# cc2650_rev1-1.net
KiCad netlist of a schematic drawn in EAGLE
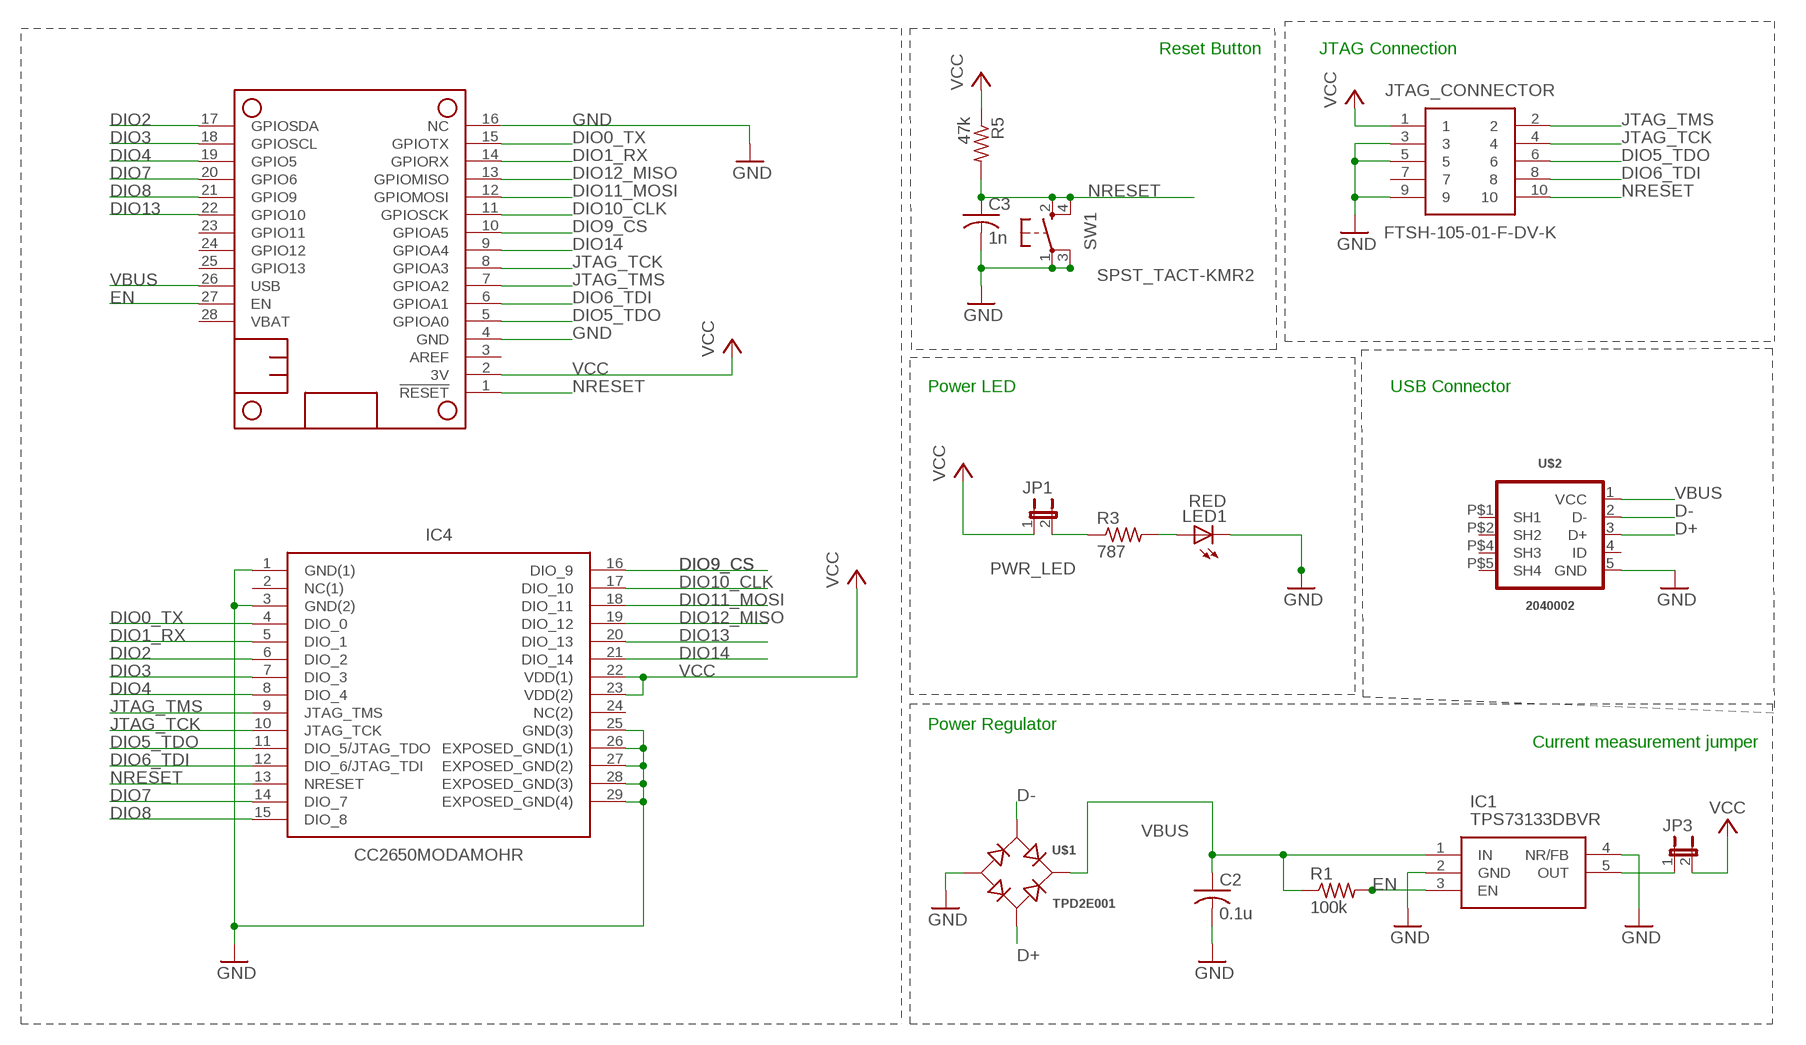
[diagram p0: schematic, sheet 1]
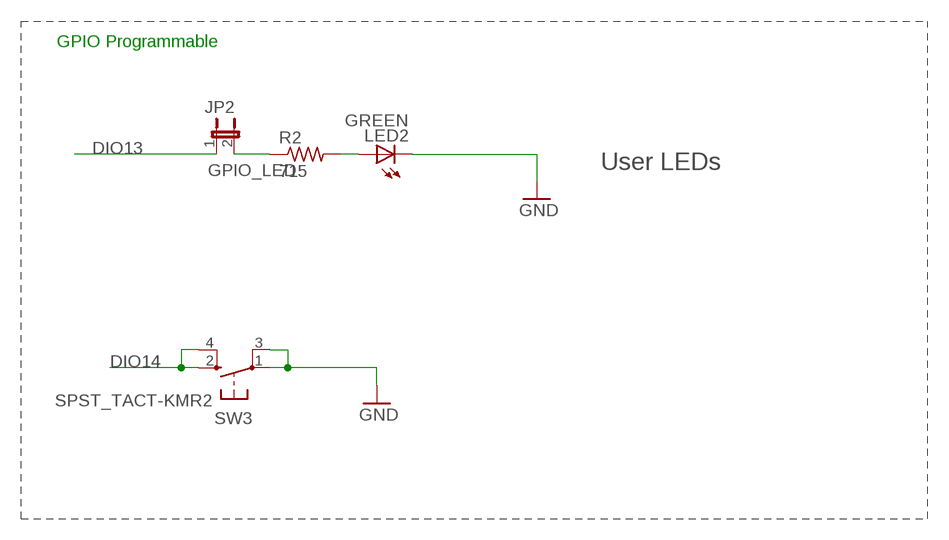
[diagram p1: schematic, sheet 2]

(export (version "E")
  (design (tool "Eeschema 10.0.6"))
  (components
    (comp (ref "C2")
      (value "0.1u")
      (footprint "eagle-import:C1206")
      (fields (field (name "MF") "VISHAY/VITRAMON") (field (name "MPN") "VJ1206Y102KXBAC"))
      (libsource (lib "eagle-import") (part "C-USC1206"))
    )
    (comp (ref "C3")
      (value "1n")
      (footprint "eagle-import:C1206")
      (fields (field (name "MF") "VISHAY/VITRAMON") (field (name "MPN") "VJ1206Y102KXBAC"))
      (libsource (lib "eagle-import") (part "C-USC1206"))
    )
    (comp (ref "IC1")
      (value "TPS73133DBVR")
      (footprint "eagle-import:SOT95P280X145-5N")
      (fields (field (name "RS_PART_NUMBER") "6613970"))
      (libsource (lib "eagle-import") (part "TPS73133DBVR"))
    )
    (comp (ref "IC4")
      (value "CC2650MODAMOHR")
      (footprint "eagle-import:MOH0029A")
      (libsource (lib "eagle-import") (part "CC2650MODAMOHR"))
    )
    (comp (ref "JP1")
      (value "PWR_LED")
      (footprint "eagle-import:JP1M")
      (fields (field (name "MPN") "2211S-02G"))
      (libsource (lib "eagle-import") (part "JP1M"))
    )
    (comp (ref "JP3")
      (value "PWR_LED")
      (footprint "eagle-import:JP1M")
      (fields (field (name "MPN") "2211S-02G"))
      (libsource (lib "eagle-import") (part "JP1M"))
    )
    (comp (ref "JTAG_CONNECTOR")
      (value "FTSH-105-01-F-DV-K")
      (footprint "eagle-import:SAMTEC_FTSH-105-01-L-DV")
      (libsource (lib "eagle-import") (part "FTSH-105-01-F-DV-K"))
    )
    (comp (ref "LED1")
      (value "RED")
      (footprint "eagle-import:CHIPLED_1206")
      (fields (field (name "MPN") "HSMC-C150"))
      (libsource (lib "eagle-import") (part "LEDCHIPLED_1206"))
    )
    (comp (ref "MS1")
      (value "FEATHERWING_NODIM")
      (footprint "eagle-import:FEATHERWING_DIM")
      (libsource (lib "eagle-import") (part "FEATHERWING_NODIM"))
    )
    (comp (ref "R1")
      (value "100k")
      (footprint "eagle-import:R1206")
      (fields (field (name "MPN") "CR1206-FX-4700ELF"))
      (libsource (lib "eagle-import") (part "R-US_R1206"))
    )
    (comp (ref "R3")
      (value "787")
      (footprint "eagle-import:R1206")
      (fields (field (name "MPN") "CR1206-FX-4700ELF"))
      (libsource (lib "eagle-import") (part "R-US_R1206"))
    )
    (comp (ref "R5")
      (value "47k")
      (footprint "eagle-import:R1206")
      (fields (field (name "MF") "VISHAY/DALE") (field (name "MPN") "CRCW120647K0FKTA"))
      (libsource (lib "eagle-import") (part "R-US_R1206"))
    )
    (comp (ref "SW1")
      (value "SPST_TACT-KMR2")
      (footprint "eagle-import:KMR2")
      (fields (field (name "MPN") "KMR241G LFS"))
      (libsource (lib "eagle-import") (part "SPST_TACT-KMR2"))
    )
    (comp (ref "U$1")
      (value "TPD2E001")
      (footprint "eagle-import:SOT-143")
      (libsource (lib "eagle-import") (part "TPD2E001"))
    )
    (comp (ref "U$2")
      (value "2040002")
      (footprint "eagle-import:2040002")
      (libsource (lib "eagle-import") (part "2040002"))
    )
    (comp (ref "JP2")
      (value "GPIO_LED")
      (footprint "eagle-import:JP1M")
      (fields (field (name "MPN") "2211S-02G"))
      (libsource (lib "eagle-import") (part "JP1M"))
    )
    (comp (ref "LED2")
      (value "GREEN")
      (footprint "eagle-import:CHIPLED_1206")
      (fields (field (name "MPN") "HSMC-C150"))
      (libsource (lib "eagle-import") (part "LEDCHIPLED_1206"))
    )
    (comp (ref "R2")
      (value "715")
      (footprint "eagle-import:R1206")
      (fields (field (name "MPN") "CR1206-FX-4700ELF"))
      (libsource (lib "eagle-import") (part "R-US_R1206"))
    )
    (comp (ref "SW3")
      (value "SPST_TACT-KMR2")
      (footprint "eagle-import:KMR2")
      (fields (field (name "MPN") "KMR241G LFS"))
      (libsource (lib "eagle-import") (part "SPST_TACT-KMR2"))
    )
  )
  (nets
    (net (code "1") (name "D+") (class "Default")
      (node (ref "U$1") (pin "3") (pinfunction "AC2_3") (pintype "passive"))
      (node (ref "U$2") (pin "3") (pinfunction "D+_3") (pintype "bidirectional"))
    )
    (net (code "2") (name "D-") (class "Default")
      (node (ref "U$1") (pin "2") (pinfunction "AC1_2") (pintype "passive"))
      (node (ref "U$2") (pin "2") (pinfunction "D-_2") (pintype "bidirectional"))
    )
    (net (code "3") (name "DIO0_TX") (class "Default")
      (node (ref "IC4") (pin "4") (pinfunction "DIO_0_4") (pintype "passive"))
      (node (ref "MS1") (pin "15") (pinfunction "GPIOTX_15") (pintype "bidirectional"))
    )
    (net (code "4") (name "DIO1_RX") (class "Default")
      (node (ref "IC4") (pin "5") (pinfunction "DIO_1_5") (pintype "passive"))
      (node (ref "MS1") (pin "14") (pinfunction "GPIORX_14") (pintype "bidirectional"))
    )
    (net (code "5") (name "DIO2") (class "Default")
      (node (ref "IC4") (pin "6") (pinfunction "DIO_2_6") (pintype "passive"))
      (node (ref "MS1") (pin "17") (pinfunction "GPIOSDA_17") (pintype "bidirectional"))
    )
    (net (code "6") (name "DIO3") (class "Default")
      (node (ref "IC4") (pin "7") (pinfunction "DIO_3_7") (pintype "passive"))
      (node (ref "MS1") (pin "18") (pinfunction "GPIOSCL_18") (pintype "bidirectional"))
    )
    (net (code "7") (name "DIO4") (class "Default")
      (node (ref "IC4") (pin "8") (pinfunction "DIO_4_8") (pintype "passive"))
      (node (ref "MS1") (pin "19") (pinfunction "GPIO5_19") (pintype "bidirectional"))
    )
    (net (code "8") (name "DIO5_TDO") (class "Default")
      (node (ref "IC4") (pin "11") (pinfunction "DIO_5/JTAG_TDO_11") (pintype "passive"))
      (node (ref "JTAG_CONNECTOR") (pin "6") (pinfunction "6_6") (pintype "passive"))
      (node (ref "MS1") (pin "5") (pinfunction "GPIOA0_5") (pintype "bidirectional"))
    )
    (net (code "9") (name "DIO6_TDI") (class "Default")
      (node (ref "IC4") (pin "12") (pinfunction "DIO_6/JTAG_TDI_12") (pintype "passive"))
      (node (ref "JTAG_CONNECTOR") (pin "8") (pinfunction "8_8") (pintype "passive"))
      (node (ref "MS1") (pin "6") (pinfunction "GPIOA1_6") (pintype "bidirectional"))
    )
    (net (code "10") (name "DIO7") (class "Default")
      (node (ref "IC4") (pin "14") (pinfunction "DIO_7_14") (pintype "passive"))
      (node (ref "MS1") (pin "20") (pinfunction "GPIO6_20") (pintype "bidirectional"))
    )
    (net (code "11") (name "DIO8") (class "Default")
      (node (ref "IC4") (pin "15") (pinfunction "DIO_8_15") (pintype "passive"))
      (node (ref "MS1") (pin "21") (pinfunction "GPIO9_21") (pintype "bidirectional"))
    )
    (net (code "12") (name "DIO9_CS") (class "Default")
      (node (ref "IC4") (pin "16") (pinfunction "DIO_9_16") (pintype "passive"))
      (node (ref "MS1") (pin "10") (pinfunction "GPIOA5_10") (pintype "bidirectional"))
    )
    (net (code "13") (name "DIO10_CLK") (class "Default")
      (node (ref "IC4") (pin "17") (pinfunction "DIO_10_17") (pintype "passive"))
      (node (ref "MS1") (pin "11") (pinfunction "GPIOSCK_11") (pintype "bidirectional"))
    )
    (net (code "14") (name "DIO11_MOSI") (class "Default")
      (node (ref "IC4") (pin "18") (pinfunction "DIO_11_18") (pintype "passive"))
      (node (ref "MS1") (pin "12") (pinfunction "GPIOMOSI_12") (pintype "bidirectional"))
    )
    (net (code "15") (name "DIO12_MISO") (class "Default")
      (node (ref "IC4") (pin "19") (pinfunction "DIO_12_19") (pintype "passive"))
      (node (ref "MS1") (pin "13") (pinfunction "GPIOMISO_13") (pintype "bidirectional"))
    )
    (net (code "16") (name "DIO13") (class "Default")
      (node (ref "IC4") (pin "20") (pinfunction "DIO_13_20") (pintype "passive"))
      (node (ref "JP2") (pin "1") (pinfunction "1_1") (pintype "passive"))
      (node (ref "MS1") (pin "22") (pinfunction "GPIO10_22") (pintype "bidirectional"))
    )
    (net (code "17") (name "DIO14") (class "Default")
      (node (ref "IC4") (pin "21") (pinfunction "DIO_14_21") (pintype "passive"))
      (node (ref "MS1") (pin "9") (pinfunction "GPIOA4_9") (pintype "bidirectional"))
      (node (ref "SW3") (pin "2") (pinfunction "S_2") (pintype "passive"))
      (node (ref "SW3") (pin "4") (pinfunction "S1_4") (pintype "passive"))
    )
    (net (code "18") (name "EN") (class "Default")
      (node (ref "IC1") (pin "3") (pinfunction "EN_3") (pintype "input"))
      (node (ref "MS1") (pin "27") (pinfunction "EN_27") (pintype "passive"))
      (node (ref "R1") (pin "2") (pinfunction "2_2") (pintype "passive"))
    )
    (net (code "19") (name "GND") (class "Default")
      (node (ref "C2") (pin "2") (pinfunction "2_2") (pintype "passive"))
      (node (ref "C3") (pin "2") (pinfunction "2_2") (pintype "passive"))
      (node (ref "IC1") (pin "2") (pinfunction "GND_2") (pintype "input"))
      (node (ref "IC1") (pin "4") (pinfunction "NR/FB_4") (pintype "input"))
      (node (ref "IC4") (pin "1") (pinfunction "GND(1)_1") (pintype "passive"))
      (node (ref "IC4") (pin "25") (pinfunction "GND(3)_25") (pintype "passive"))
      (node (ref "IC4") (pin "26") (pinfunction "EXPOSED_GND(1)_26") (pintype "passive"))
      (node (ref "IC4") (pin "27") (pinfunction "EXPOSED_GND(2)_27") (pintype "passive"))
      (node (ref "IC4") (pin "28") (pinfunction "EXPOSED_GND(3)_28") (pintype "passive"))
      (node (ref "IC4") (pin "29") (pinfunction "EXPOSED_GND(4)_29") (pintype "passive"))
      (node (ref "IC4") (pin "3") (pinfunction "GND(2)_3") (pintype "passive"))
      (node (ref "JTAG_CONNECTOR") (pin "3") (pinfunction "3_3") (pintype "passive"))
      (node (ref "JTAG_CONNECTOR") (pin "5") (pinfunction "5_5") (pintype "passive"))
      (node (ref "JTAG_CONNECTOR") (pin "9") (pinfunction "9_9") (pintype "passive"))
      (node (ref "LED1") (pin "C") (pinfunction "C_C") (pintype "passive"))
      (node (ref "LED2") (pin "C") (pinfunction "C_C") (pintype "passive"))
      (node (ref "MS1") (pin "16") (pinfunction "NC_16") (pintype "passive"))
      (node (ref "MS1") (pin "4") (pinfunction "GND_4") (pintype "power_in"))
      (node (ref "SW1") (pin "1") (pinfunction "P_1") (pintype "passive"))
      (node (ref "SW1") (pin "3") (pinfunction "P1_3") (pintype "passive"))
      (node (ref "SW3") (pin "1") (pinfunction "P_1") (pintype "passive"))
      (node (ref "SW3") (pin "3") (pinfunction "P1_3") (pintype "passive"))
      (node (ref "U$1") (pin "1") (pinfunction "-_1") (pintype "passive"))
      (node (ref "U$2") (pin "5") (pinfunction "GND_5") (pintype "bidirectional"))
    )
    (net (code "20") (name "JTAG_TCK") (class "Default")
      (node (ref "IC4") (pin "10") (pinfunction "JTAG_TCK_10") (pintype "passive"))
      (node (ref "JTAG_CONNECTOR") (pin "4") (pinfunction "4_4") (pintype "passive"))
      (node (ref "MS1") (pin "8") (pinfunction "GPIOA3_8") (pintype "bidirectional"))
    )
    (net (code "21") (name "JTAG_TMS") (class "Default")
      (node (ref "IC4") (pin "9") (pinfunction "JTAG_TMS_9") (pintype "passive"))
      (node (ref "JTAG_CONNECTOR") (pin "2") (pinfunction "2_2") (pintype "passive"))
      (node (ref "MS1") (pin "7") (pinfunction "GPIOA2_7") (pintype "bidirectional"))
    )
    (net (code "22") (name "NRESET") (class "Default")
      (node (ref "C3") (pin "1") (pinfunction "1_1") (pintype "passive"))
      (node (ref "IC4") (pin "13") (pinfunction "NRESET_13") (pintype "passive"))
      (node (ref "JTAG_CONNECTOR") (pin "10") (pinfunction "10_10") (pintype "passive"))
      (node (ref "MS1") (pin "1") (pinfunction "~{RESET}_1") (pintype "input"))
      (node (ref "R5") (pin "2") (pinfunction "2_2") (pintype "passive"))
      (node (ref "SW1") (pin "2") (pinfunction "S_2") (pintype "passive"))
      (node (ref "SW1") (pin "4") (pinfunction "S1_4") (pintype "passive"))
    )
    (net (code "23") (name "Net-(IC1-OUT)") (class "Default")
      (node (ref "IC1") (pin "5") (pinfunction "OUT_5") (pintype "input"))
      (node (ref "JP3") (pin "1") (pinfunction "1_1") (pintype "passive"))
    )
    (net (code "24") (name "Net-(JP1-Pad2)") (class "Default")
      (node (ref "JP1") (pin "2") (pinfunction "2_2") (pintype "passive"))
      (node (ref "R3") (pin "1") (pinfunction "1_1") (pintype "passive"))
    )
    (net (code "25") (name "Net-(JP2-Pad2)") (class "Default")
      (node (ref "JP2") (pin "2") (pinfunction "2_2") (pintype "passive"))
      (node (ref "R2") (pin "1") (pinfunction "1_1") (pintype "passive"))
    )
    (net (code "26") (name "Net-(LED1-PadA)") (class "Default")
      (node (ref "LED1") (pin "A") (pinfunction "A_A") (pintype "passive"))
      (node (ref "R3") (pin "2") (pinfunction "2_2") (pintype "passive"))
    )
    (net (code "27") (name "Net-(LED2-PadA)") (class "Default")
      (node (ref "LED2") (pin "A") (pinfunction "A_A") (pintype "passive"))
      (node (ref "R2") (pin "2") (pinfunction "2_2") (pintype "passive"))
    )
    (net (code "28") (name "VBAT") (class "Default")
      (node (ref "MS1") (pin "28") (pinfunction "VBAT_28") (pintype "power_in"))
    )
    (net (code "29") (name "VBUS") (class "Default")
      (node (ref "C2") (pin "1") (pinfunction "1_1") (pintype "passive"))
      (node (ref "IC1") (pin "1") (pinfunction "IN_1") (pintype "input"))
      (node (ref "MS1") (pin "26") (pinfunction "USB_26") (pintype "power_in"))
      (node (ref "R1") (pin "1") (pinfunction "1_1") (pintype "passive"))
      (node (ref "U$1") (pin "4") (pinfunction "+_4") (pintype "passive"))
      (node (ref "U$2") (pin "1") (pinfunction "VCC_1") (pintype "bidirectional"))
    )
    (net (code "30") (name "VCC") (class "Default")
      (node (ref "IC4") (pin "22") (pinfunction "VDD(1)_22") (pintype "passive"))
      (node (ref "IC4") (pin "23") (pinfunction "VDD(2)_23") (pintype "passive"))
      (node (ref "JP1") (pin "1") (pinfunction "1_1") (pintype "passive"))
      (node (ref "JP3") (pin "2") (pinfunction "2_2") (pintype "passive"))
      (node (ref "JTAG_CONNECTOR") (pin "1") (pinfunction "1_1") (pintype "passive"))
      (node (ref "MS1") (pin "2") (pinfunction "3V_2") (pintype "power_in"))
      (node (ref "R5") (pin "1") (pinfunction "1_1") (pintype "passive"))
    )
    (net (code "31") (name "unconnected-(IC4-NC(1)-Pad2)") (class "Default")
      (node (ref "IC4") (pin "2") (pinfunction "NC(1)_2") (pintype "passive"))
    )
    (net (code "32") (name "unconnected-(IC4-NC(2)-Pad24)") (class "Default")
      (node (ref "IC4") (pin "24") (pinfunction "NC(2)_24") (pintype "passive"))
    )
    (net (code "33") (name "unconnected-(JTAG_CONNECTOR-Pad7)") (class "Default")
      (node (ref "JTAG_CONNECTOR") (pin "7") (pinfunction "7_7") (pintype "passive"))
    )
    (net (code "34") (name "unconnected-(MS1-AREF-Pad3)") (class "Default")
      (node (ref "MS1") (pin "3") (pinfunction "AREF_3") (pintype "passive"))
    )
    (net (code "35") (name "unconnected-(MS1-GPIO11-Pad23)") (class "Default")
      (node (ref "MS1") (pin "23") (pinfunction "GPIO11_23") (pintype "bidirectional"))
    )
    (net (code "36") (name "unconnected-(MS1-GPIO12-Pad24)") (class "Default")
      (node (ref "MS1") (pin "24") (pinfunction "GPIO12_24") (pintype "bidirectional"))
    )
    (net (code "37") (name "unconnected-(MS1-GPIO13-Pad25)") (class "Default")
      (node (ref "MS1") (pin "25") (pinfunction "GPIO13_25") (pintype "bidirectional"))
    )
    (net (code "38") (name "unconnected-(U$2-ID-Pad4)") (class "Default")
      (node (ref "U$2") (pin "4") (pinfunction "ID_4") (pintype "bidirectional"))
    )
    (net (code "39") (name "unconnected-(U$2-SH1-PadP$1)") (class "Default")
      (node (ref "U$2") (pin "P$1") (pinfunction "SH1_P$1") (pintype "no_connect"))
    )
    (net (code "40") (name "unconnected-(U$2-SH2-PadP$2)") (class "Default")
      (node (ref "U$2") (pin "P$2") (pinfunction "SH2_P$2") (pintype "no_connect"))
    )
    (net (code "41") (name "unconnected-(U$2-SH3-PadP$4)") (class "Default")
      (node (ref "U$2") (pin "P$4") (pinfunction "SH3_P$4") (pintype "no_connect"))
    )
    (net (code "42") (name "unconnected-(U$2-SH4-PadP$5)") (class "Default")
      (node (ref "U$2") (pin "P$5") (pinfunction "SH4_P$5") (pintype "no_connect"))
    )
  )
)
